# 4_Digital_Isolator.net
KiCad netlist of a schematic drawn in Altium Designer
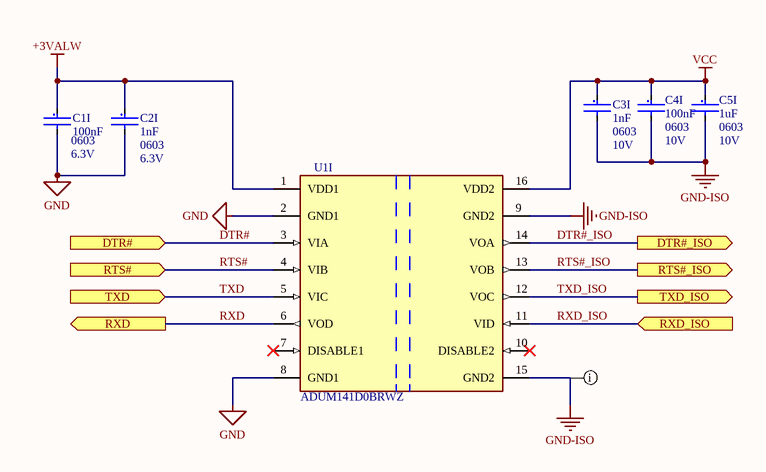
[diagram p0: 4_Digital_Isolator.SchDoc]

(export (version "E")
  (design (tool "Eeschema 10.0.6"))
  (components
    (comp (ref "C1I")
      (value "100nF")
      (footprint "C0603-IPC_C_No_Silk")
      (description "Cap Cer 0.1UF 6.3V X7R 0603")
      (fields
        (field (name "MANUFACTURER") "KYOCERA AVX")
        (field (name "MANUFACTURER PART NUMBER") "KGM15AR70J104KM")
        (field (name "VOLTAGE") "6.3V")
        (field (name "PACKAGE") "0603")
      )
      (libsource (lib "Lib_Capacitor_0603") (part "100nF_6.3V"))
    )
    (comp (ref "C2I")
      (value "1nF")
      (footprint "C0603-IPC_C_No_Silk")
      (description "Cap Ceramic 0.001uF 6.3V C0G 10% SMD 0603 125°C Paper T/R")
      (fields
        (field (name "MANUFACTURER") "Kyocera AVX")
        (field (name "MANUFACTURER PART NUMBER") "06036A102KAT2A")
        (field (name "CASE CODE (IMPERIAL)") "0603")
        (field (name "VOLTAGE RATING") "6.3V")
      )
      (libsource (lib "Lib_Capacitor_0603") (part "1nF_6.3V"))
    )
    (comp (ref "C3I")
      (value "1nF")
      (footprint "C0603-IPC_C_No_Silk")
      (description "Cap Ceramic 0.001uF 10V X7R 10% SMD 0603 125°C Paper T/R")
      (fields
        (field (name "MANUFACTURER") "Yageo")
        (field (name "MANUFACTURER PART NUMBER") "CC0603KRX7R6BB102")
        (field (name "CASE CODE (IMPERIAL)") "0603")
        (field (name "VOLTAGE RATING") "10V")
      )
      (libsource (lib "Lib_Capacitor_0603") (part "1nF_10V"))
    )
    (comp (ref "C4I")
      (value "100nF")
      (footprint "C0603-IPC_C_No_Silk")
      (description "Multilayer Ceramic Capacitor, 0.1 uF, 10 V, ± 10%, X7R, 0603 [1608 Metric]")
      (fields
        (field (name "MANUFACTURER") "KEMET")
        (field (name "MANUFACTURER PART NUMBER") "C0603C104K8RACTU")
        (field (name "VOLTAGE") "10V")
        (field (name "CASE/PACKAGE") "0603")
      )
      (libsource (lib "Lib_Capacitor_0603") (part "100nF_10V"))
    )
    (comp (ref "C5I")
      (value "1uF")
      (footprint "C0603-IPC_C_No_Silk")
      (description "Ceramic Capacitor, Multilayer, Ceramic, 10V, 10% +Tol, 10% -Tol, X5R, 15% TC, 1uF, 0603")
      (fields
        (field (name "MANUFACTURER") "KEMET")
        (field (name "MANUFACTURER PART NUMBER") "C0603C105K8PACTU")
        (field (name "VOLTAGE") "10V")
        (field (name "CASE/PACKAGE") "0603")
      )
      (libsource (lib "Lib_Capacitor_0603") (part "1uF_10V"))
    )
    (comp (ref "U1I")
      (value "ADUM141D0BRWZ")
      (footprint "SOIC-W-16-IPC_A")
      (description "DGTL ISO 3750VRMS 4CH GP 16SOIC")
      (libsource (lib "Lib_IC_Voltage_Level_Shift") (part "ADUM141D0BRWZ"))
    )
  )
  (nets
    (net (code "1") (name "+3VALW") (class "Default")
      (node (ref "C1I") (pin "1") (pinfunction "1_1") (pintype "passive"))
      (node (ref "C2I") (pin "1") (pinfunction "1_1") (pintype "passive"))
      (node (ref "U1I") (pin "1") (pinfunction "VDD1_1") (pintype "power_in"))
    )
    (net (code "2") (name "/DTR#") (class "Default")
      (node (ref "U1I") (pin "3") (pinfunction "VIA_3") (pintype "input"))
    )
    (net (code "3") (name "/DTR#_ISO") (class "Default")
      (node (ref "U1I") (pin "14") (pinfunction "VOA_14") (pintype "output"))
    )
    (net (code "4") (name "/RTS#") (class "Default")
      (node (ref "U1I") (pin "4") (pinfunction "VIB_4") (pintype "input"))
    )
    (net (code "5") (name "/RTS#_ISO") (class "Default")
      (node (ref "U1I") (pin "13") (pinfunction "VOB_13") (pintype "output"))
    )
    (net (code "6") (name "/RXD") (class "Default")
      (node (ref "U1I") (pin "6") (pinfunction "VOD_6") (pintype "output"))
    )
    (net (code "7") (name "/RXD_ISO") (class "Default")
      (node (ref "U1I") (pin "11") (pinfunction "VID_11") (pintype "input"))
    )
    (net (code "8") (name "/TXD") (class "Default")
      (node (ref "U1I") (pin "5") (pinfunction "VIC_5") (pintype "input"))
    )
    (net (code "9") (name "/TXD_ISO") (class "Default")
      (node (ref "U1I") (pin "12") (pinfunction "VOC_12") (pintype "output"))
    )
    (net (code "10") (name "GND") (class "Default")
      (node (ref "C1I") (pin "2") (pinfunction "2_2") (pintype "passive"))
      (node (ref "C2I") (pin "2") (pinfunction "2_2") (pintype "passive"))
      (node (ref "U1I") (pin "2") (pinfunction "GND1_2") (pintype "power_in"))
      (node (ref "U1I") (pin "8") (pinfunction "GND1_8") (pintype "power_in"))
    )
    (net (code "11") (name "GND-ISO") (class "Default")
      (node (ref "C3I") (pin "2") (pinfunction "2_2") (pintype "passive"))
      (node (ref "C4I") (pin "2") (pinfunction "2_2") (pintype "passive"))
      (node (ref "C5I") (pin "2") (pinfunction "2_2") (pintype "passive"))
      (node (ref "U1I") (pin "15") (pinfunction "GND2_15") (pintype "power_in"))
      (node (ref "U1I") (pin "9") (pinfunction "GND2_9") (pintype "power_in"))
    )
    (net (code "12") (name "VCC") (class "Default")
      (node (ref "C3I") (pin "1") (pinfunction "1_1") (pintype "passive"))
      (node (ref "C4I") (pin "1") (pinfunction "1_1") (pintype "passive"))
      (node (ref "C5I") (pin "1") (pinfunction "1_1") (pintype "passive"))
      (node (ref "U1I") (pin "16") (pinfunction "VDD2_16") (pintype "power_in"))
    )
    (net (code "13") (name "unconnected-(U1I-DISABLE1-Pad7)") (class "Default")
      (node (ref "U1I") (pin "7") (pinfunction "DISABLE1_7") (pintype "input+no_connect"))
    )
    (net (code "14") (name "unconnected-(U1I-DISABLE2-Pad10)") (class "Default")
      (node (ref "U1I") (pin "10") (pinfunction "DISABLE2_10") (pintype "input+no_connect"))
    )
  )
)
